# 06_Power.net
KiCad netlist of a schematic drawn in Altium Designer
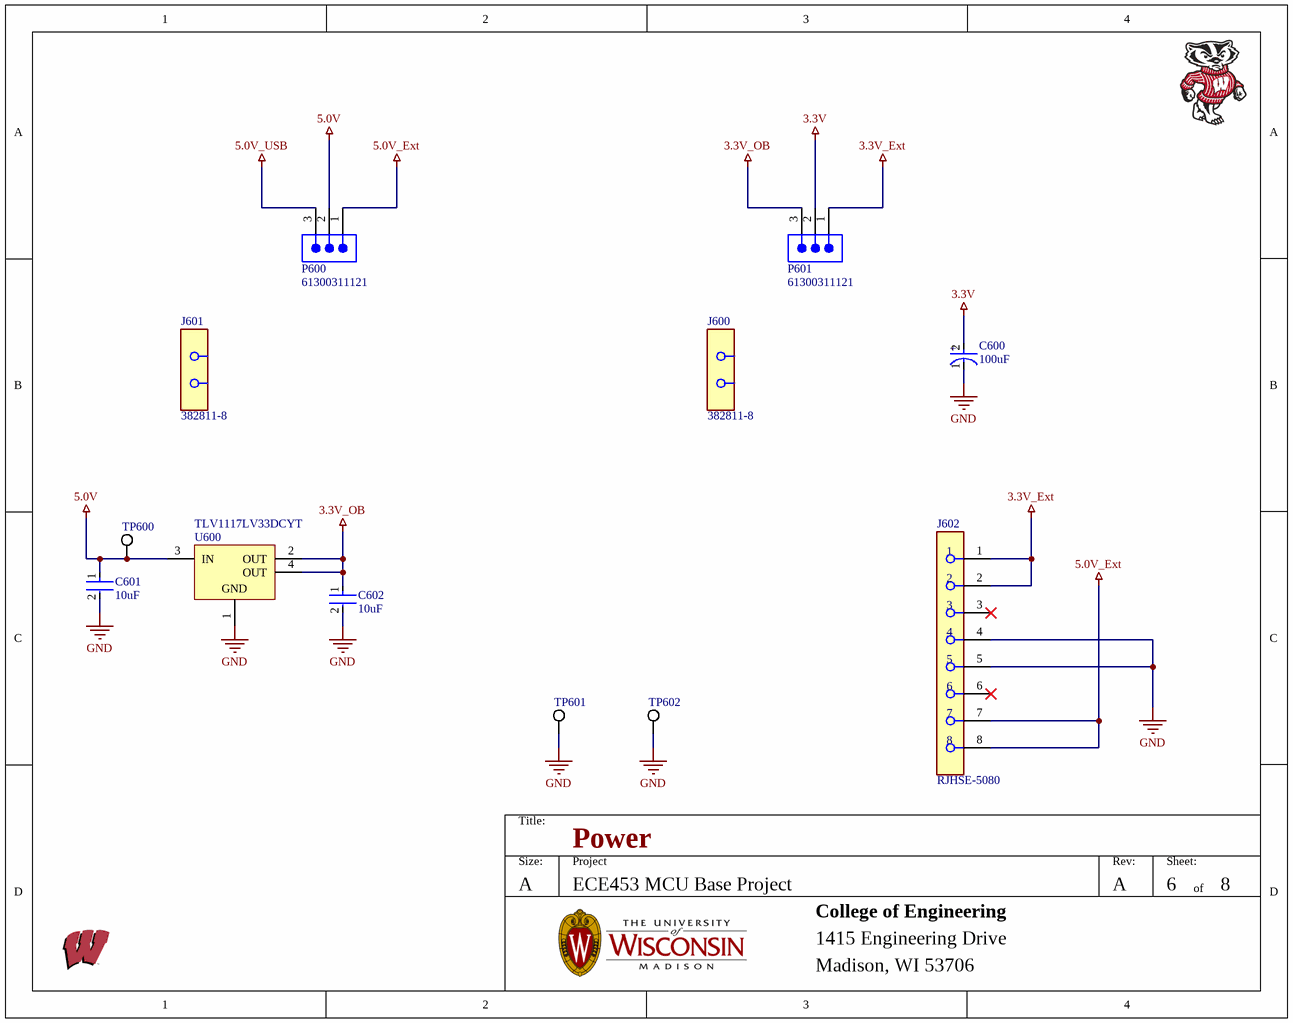
[diagram p0: 06_Power.SchDoc]

(export (version "E")
  (design (tool "Eeschema 10.0.6"))
  (components
    (comp (ref "C600")
      (value "100uF")
      (footprint "FP-SD8-MFG")
      (description "CAP ALUM 100UF 20% 25V SMD")
      (fields (field (name "VOLTAGE") "25V") (field (name "TOLERANCE") "20%"))
      (libsource (lib "Altium Content Vault") (part "a00bbbee19879c290e62620ae7e47b1"))
    )
    (comp (ref "C601")
      (value "10uF")
      (footprint "FP-C0805C-DG-MFG")
      (description "CAP CER 10UF 10V X5R 0805")
      (fields (field (name "TOLERANCE") "10%") (field (name "MANUFACTURER PART NUMBER") "C0805C106K8PACTU"))
      (libsource (lib "Altium Content Vault") (part "11868f565c42a9108669ba33697ecf6"))
    )
    (comp (ref "C602")
      (value "10uF")
      (footprint "FP-C0805C-DG-MFG")
      (description "CAP CER 10UF 10V X5R 0805")
      (fields (field (name "TOLERANCE") "10%") (field (name "MANUFACTURER PART NUMBER") "C0805C106K8PACTU"))
      (libsource (lib "Altium Content Vault") (part "11868f565c42a9108669ba33697ecf6"))
    )
    (comp (ref "J600")
      (value "382811-8")
      (footprint "FP-382811-8-MFG")
      (description "CONN SHUNT 2POS OPEN 2.54MM")
      (libsource (lib "Altium Content Vault") (part "eeee4e7e6eb3933c9cad7704fdbd1a5"))
    )
    (comp (ref "J601")
      (value "382811-8")
      (footprint "FP-382811-8-MFG")
      (description "CONN SHUNT 2POS OPEN 2.54MM")
      (libsource (lib "Altium Content Vault") (part "eeee4e7e6eb3933c9cad7704fdbd1a5"))
    )
    (comp (ref "J602")
      (value "RJHSE-5080")
      (footprint "FP-RJHSE-5080-MFG")
      (description "CONN MOD JACK 8P8C R/A UNSHLD")
      (fields
        (field (name "OCTOPART") "https://octopart.com/rjhse-5080-amphenol-45060")
        (field (name "MANUFACTURER") "Amphenol")
      )
      (libsource (lib "Altium Content Vault") (part "b0a0b555dd3abf3683e7c330df25cc4"))
    )
    (comp (ref "P600")
      (value "61300311121")
      (footprint "61300311121")
      (libsource (lib "Altium Content Vault") (part "Header_Male_1R_03P"))
    )
    (comp (ref "P601")
      (value "61300311121")
      (footprint "61300311121")
      (libsource (lib "Altium Content Vault") (part "Header_Male_1R_03P"))
    )
    (comp (ref "TP600")
      (value "~")
      (footprint "KSTN-5019_V")
      (description "Test Point, 1 Position SMD, RoHS, Tape and Reel")
      (libsource (lib "Altium Content Vault") (part "TESTPOINT_WHITE"))
    )
    (comp (ref "TP601")
      (value "~")
      (footprint "KSTN-5019_V")
      (description "Test Point, 1 Position SMD, RoHS, Tape and Reel")
      (libsource (lib "Altium Content Vault") (part "TESTPOINT_WHITE"))
    )
    (comp (ref "TP602")
      (value "~")
      (footprint "KSTN-5019_V")
      (description "Test Point, 1 Position SMD, RoHS, Tape and Reel")
      (libsource (lib "Altium Content Vault") (part "TESTPOINT_WHITE"))
    )
    (comp (ref "U600")
      (value "TLV1117LV33DCYT")
      (footprint "DCY0004A_M")
      (fields (field (name "MANUFACTURER") "Texas Instruments"))
      (libsource (lib "Altium Content Vault") (part "TI-TLV1117LV33DCY4"))
    )
  )
  (nets
    (net (code "1") (name "3.3V") (class "Default")
      (node (ref "C600") (pin "2") (pinfunction "A_2") (pintype "passive"))
      (node (ref "P601") (pin "2") (pinfunction "2_2") (pintype "passive"))
    )
    (net (code "2") (name "3.3V_Ext") (class "Default")
      (node (ref "J602") (pin "1") (pinfunction "1_1") (pintype "passive"))
      (node (ref "J602") (pin "2") (pinfunction "2_2") (pintype "passive"))
      (node (ref "P601") (pin "1") (pinfunction "1_1") (pintype "passive"))
    )
    (net (code "3") (name "3.3V_OB") (class "Default")
      (node (ref "C602") (pin "1") (pinfunction "1_1") (pintype "passive"))
      (node (ref "P601") (pin "3") (pinfunction "3_3") (pintype "passive"))
      (node (ref "U600") (pin "2") (pinfunction "OUT_2") (pintype "power_in"))
      (node (ref "U600") (pin "4") (pinfunction "OUT_4") (pintype "power_in"))
    )
    (net (code "4") (name "5.0V") (class "Default")
      (node (ref "C601") (pin "1") (pinfunction "1_1") (pintype "passive"))
      (node (ref "P600") (pin "2") (pinfunction "2_2") (pintype "passive"))
      (node (ref "TP600") (pin "1") (pinfunction "1_1") (pintype "passive"))
      (node (ref "U600") (pin "3") (pinfunction "IN_3") (pintype "power_in"))
    )
    (net (code "5") (name "5.0V_Ext") (class "Default")
      (node (ref "J602") (pin "7") (pinfunction "7_7") (pintype "passive"))
      (node (ref "J602") (pin "8") (pinfunction "8_8") (pintype "passive"))
      (node (ref "P600") (pin "1") (pinfunction "1_1") (pintype "passive"))
    )
    (net (code "6") (name "5.0V_USB") (class "Default")
      (node (ref "P600") (pin "3") (pinfunction "3_3") (pintype "passive"))
    )
    (net (code "7") (name "GND") (class "Default")
      (node (ref "C600") (pin "1") (pinfunction "C_1") (pintype "passive"))
      (node (ref "C601") (pin "2") (pinfunction "2_2") (pintype "passive"))
      (node (ref "C602") (pin "2") (pinfunction "2_2") (pintype "passive"))
      (node (ref "J602") (pin "4") (pinfunction "4_4") (pintype "passive"))
      (node (ref "J602") (pin "5") (pinfunction "5_5") (pintype "passive"))
      (node (ref "TP601") (pin "1") (pinfunction "1_1") (pintype "passive"))
      (node (ref "TP602") (pin "1") (pinfunction "1_1") (pintype "passive"))
      (node (ref "U600") (pin "1") (pinfunction "GND_1") (pintype "power_in"))
    )
    (net (code "8") (name "unconnected-(J602-Pad3)") (class "Default")
      (node (ref "J602") (pin "3") (pinfunction "3_3") (pintype "passive+no_connect"))
    )
    (net (code "9") (name "unconnected-(J602-Pad6)") (class "Default")
      (node (ref "J602") (pin "6") (pinfunction "6_6") (pintype "passive+no_connect"))
    )
  )
)
